# Battery_Socket.net
KiCad netlist of a schematic drawn in Altium Designer
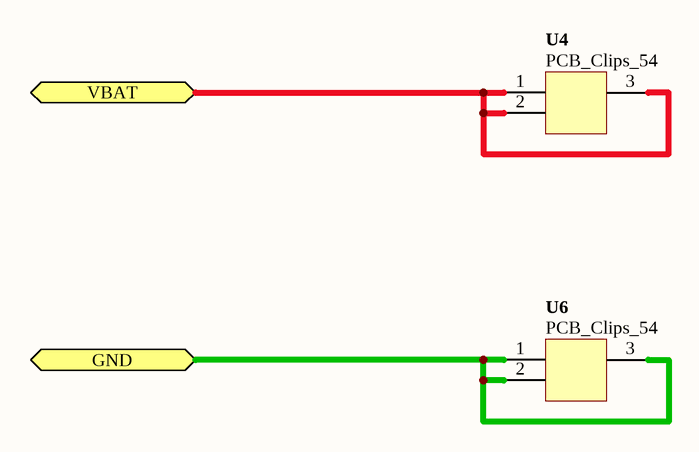
[diagram p0: Battery_Socket.SchDoc]

(export (version "E")
  (design (tool "Eeschema 10.0.6"))
  (components
    (comp (ref "U4")
      (value "PCB_Clips_54")
      (footprint "KEYSTONE-CLIPS_54-3_V")
      (description "PC Battery Clip, Catalog No.54, Spring Steel, Body 18.102 x 13.004 mm, THM")
      (fields (field (name "MANUFACTURER") "Keystone"))
      (libsource (lib "Altium Content Vault") (part "KEYSTONE-CLIPS_54-3"))
    )
    (comp (ref "U6")
      (value "PCB_Clips_54")
      (footprint "KEYSTONE-CLIPS_54-3_V")
      (description "PC Battery Clip, Catalog No.54, Spring Steel, Body 18.102 x 13.004 mm, THM")
      (fields (field (name "MANUFACTURER") "Keystone"))
      (libsource (lib "Altium Content Vault") (part "KEYSTONE-CLIPS_54-3"))
    )
  )
  (nets
    (net (code "1") (name "/GND") (class "Default")
      (node (ref "U6") (pin "1") (pinfunction "1_1") (pintype "power_in"))
      (node (ref "U6") (pin "2") (pinfunction "2_2") (pintype "passive"))
      (node (ref "U6") (pin "3") (pinfunction "3_3") (pintype "passive"))
    )
    (net (code "2") (name "/VBAT") (class "Default")
      (node (ref "U4") (pin "1") (pinfunction "1_1") (pintype "power_in"))
      (node (ref "U4") (pin "2") (pinfunction "2_2") (pintype "passive"))
      (node (ref "U4") (pin "3") (pinfunction "3_3") (pintype "passive"))
    )
  )
)
